# SparkFun_RTK_Facet_-_External_Connector.net
KiCad netlist of a schematic drawn in EAGLE
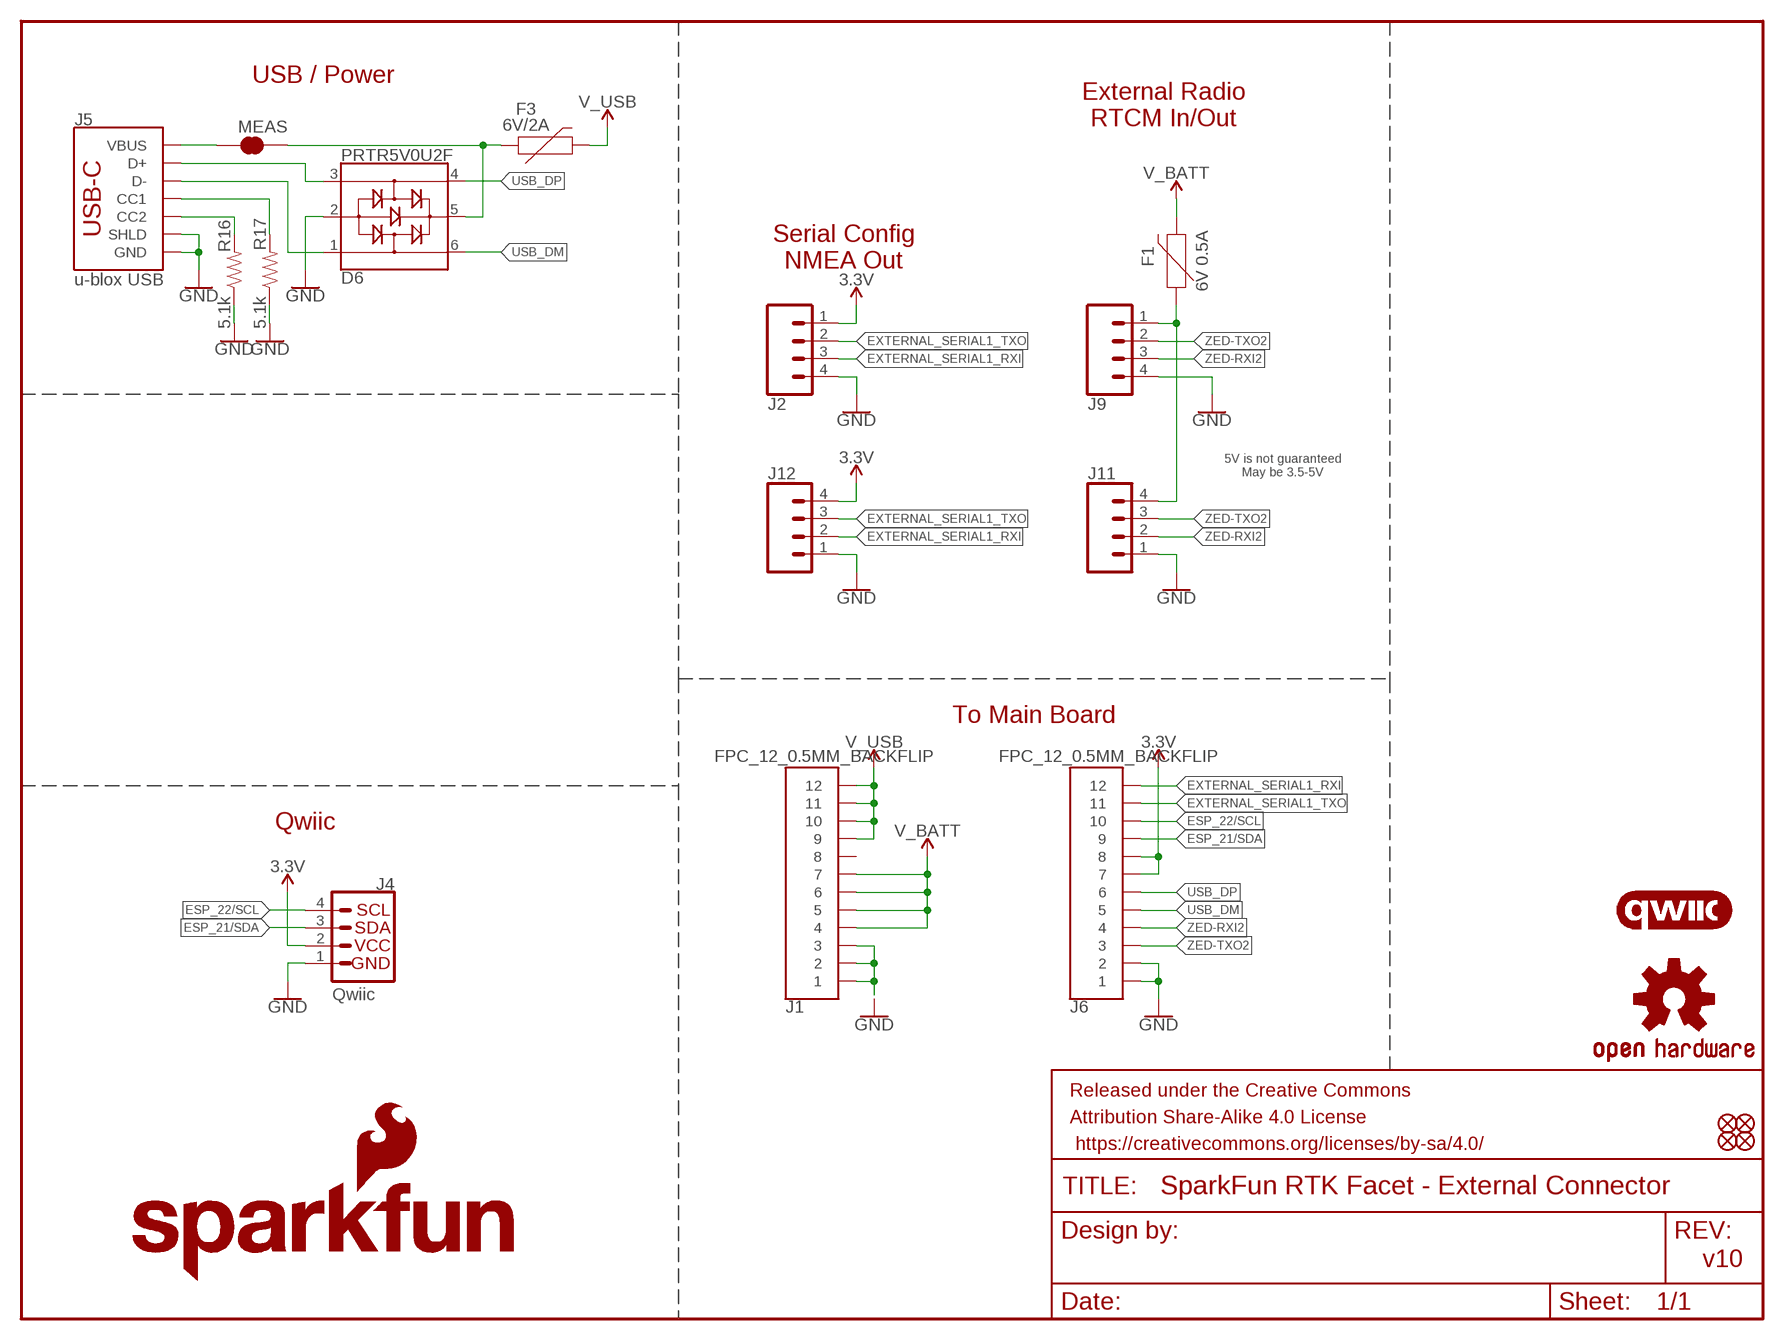
[diagram p0: schematic, sheet 1]

(export (version "E")
  (design (tool "Eeschema 10.0.6"))
  (components
    (comp (ref "D6")
      (value "PRTR5V0U2F")
      (footprint "eagle-import:SOT886")
      (libsource (lib "eagle-import") (part "PRTR5V0U2F"))
    )
    (comp (ref "F1")
      (value "6V 0.5A")
      (footprint "eagle-import:0805")
      (libsource (lib "eagle-import") (part "PPTC_6V500MA"))
    )
    (comp (ref "F3")
      (value "6V/2A")
      (footprint "eagle-import:1210")
      (libsource (lib "eagle-import") (part "PPTC_6V2A"))
    )
    (comp (ref "FRAME1")
      (value "FRAME-LETTER")
      (footprint "eagle-import:CREATIVE_COMMONS")
      (libsource (lib "eagle-import") (part "FRAME-LETTER"))
    )
    (comp (ref "J1")
      (value "FPC_12_0.5MM_BACKFLIP")
      (footprint "eagle-import:FPC_12_DOUBLESIDED_BACKFLIP")
      (libsource (lib "eagle-import") (part "FPC_12_0.5MM_BACKFLIP"))
    )
    (comp (ref "J2")
      (value "CONN_04JST-SMD-LOCKING")
      (footprint "eagle-import:JST-4-SMD-1.25MM-LOCKING")
      (libsource (lib "eagle-import") (part "CONN_04JST-SMD-LOCKING"))
    )
    (comp (ref "J4")
      (value "Qwiic")
      (footprint "eagle-import:JST04_1MM_RA")
      (libsource (lib "eagle-import") (part "I2C_STANDARDQWIIC"))
    )
    (comp (ref "J5")
      (value "u-blox USB")
      (footprint "eagle-import:USB-C-16P-2LAYER-PADS")
      (libsource (lib "eagle-import") (part "USB_C_2-LAYER_PADS"))
    )
    (comp (ref "J6")
      (value "FPC_12_0.5MM_BACKFLIP")
      (footprint "eagle-import:FPC_12_DOUBLESIDED_BACKFLIP")
      (libsource (lib "eagle-import") (part "FPC_12_0.5MM_BACKFLIP"))
    )
    (comp (ref "J9")
      (value "CONN_04JST-SMD-LOCKING")
      (footprint "eagle-import:JST-4-SMD-1.25MM-LOCKING")
      (libsource (lib "eagle-import") (part "CONN_04JST-SMD-LOCKING"))
    )
    (comp (ref "J11")
      (value "CONN_041X04_NO_SILK_NO_POP")
      (footprint "eagle-import:1X04_NO_SILK")
      (libsource (lib "eagle-import") (part "CONN_041X04_NO_SILK_NO_POP"))
    )
    (comp (ref "J12")
      (value "CONN_041X04_NO_SILK_NO_POP")
      (footprint "eagle-import:1X04_NO_SILK")
      (libsource (lib "eagle-import") (part "CONN_041X04_NO_SILK_NO_POP"))
    )
    (comp (ref "JP21")
      (value "FIDUCIALUFIDUCIAL")
      (footprint "eagle-import:FIDUCIAL-MICRO")
      (libsource (lib "eagle-import") (part "FIDUCIALUFIDUCIAL"))
    )
    (comp (ref "JP61")
      (value "FIDUCIALUFIDUCIAL")
      (footprint "eagle-import:FIDUCIAL-MICRO")
      (libsource (lib "eagle-import") (part "FIDUCIALUFIDUCIAL"))
    )
    (comp (ref "JP71")
      (value "FIDUCIALUFIDUCIAL")
      (footprint "eagle-import:FIDUCIAL-MICRO")
      (libsource (lib "eagle-import") (part "FIDUCIALUFIDUCIAL"))
    )
    (comp (ref "JP81")
      (value "FIDUCIALUFIDUCIAL")
      (footprint "eagle-import:FIDUCIAL-MICRO")
      (libsource (lib "eagle-import") (part "FIDUCIALUFIDUCIAL"))
    )
    (comp (ref "LOGO1")
      (value "OSHW-LOGOMINI")
      (footprint "eagle-import:OSHW-LOGO-MINI")
      (libsource (lib "eagle-import") (part "OSHW-LOGOMINI"))
    )
    (comp (ref "LOGO2")
      (value "SFE_LOGO_NAME_FLAME.1_INCH")
      (footprint "eagle-import:SFE_LOGO_NAME_FLAME_.1")
      (libsource (lib "eagle-import") (part "SFE_LOGO_NAME_FLAME.1_INCH"))
    )
    (comp (ref "LOGO3")
      (value "QWIIC_LOGO_CONNECTOR")
      (footprint "eagle-import:QWIIC_5.5MM")
      (libsource (lib "eagle-import") (part "QWIIC_LOGO_CONNECTOR"))
    )
    (comp (ref "MEAS")
      (value "JUMPER-COMBO_2_NC_TRACE")
      (footprint "eagle-import:COMBO-JUMPER_2_NC_TRACE")
      (libsource (lib "eagle-import") (part "JUMPER-COMBO_2_NC_TRACE"))
    )
    (comp (ref "R16")
      (value "5.1k")
      (footprint "eagle-import:0603")
      (libsource (lib "eagle-import") (part "5.1KOHM5.1KOHM-0603-1/10W-1%"))
    )
    (comp (ref "R17")
      (value "5.1k")
      (footprint "eagle-import:0603")
      (libsource (lib "eagle-import") (part "5.1KOHM5.1KOHM-0603-1/10W-1%"))
    )
  )
  (nets
    (net (code "1") (name "3.3V") (class "Default")
      (node (ref "J12") (pin "4") (pinfunction "4_4") (pintype "passive"))
      (node (ref "J2") (pin "1") (pinfunction "1_1") (pintype "passive"))
      (node (ref "J4") (pin "2") (pinfunction "2_2") (pintype "power_in"))
      (node (ref "J6") (pin "7") (pinfunction "7_7") (pintype "bidirectional"))
      (node (ref "J6") (pin "8") (pinfunction "8_8") (pintype "bidirectional"))
    )
    (net (code "2") (name "ESP_21{slash}SDA") (class "Default")
      (node (ref "J4") (pin "3") (pinfunction "3_3") (pintype "passive"))
      (node (ref "J6") (pin "9") (pinfunction "9_9") (pintype "bidirectional"))
    )
    (net (code "3") (name "ESP_22{slash}SCL") (class "Default")
      (node (ref "J4") (pin "4") (pinfunction "4_4") (pintype "passive"))
      (node (ref "J6") (pin "10") (pinfunction "10_10") (pintype "bidirectional"))
    )
    (net (code "4") (name "EXTERNAL_SERIAL1_RXI") (class "Default")
      (node (ref "J12") (pin "2") (pinfunction "2_2") (pintype "passive"))
      (node (ref "J2") (pin "3") (pinfunction "3_3") (pintype "passive"))
      (node (ref "J6") (pin "12") (pinfunction "12_12") (pintype "bidirectional"))
    )
    (net (code "5") (name "EXTERNAL_SERIAL1_TXO") (class "Default")
      (node (ref "J12") (pin "3") (pinfunction "3_3") (pintype "passive"))
      (node (ref "J2") (pin "2") (pinfunction "2_2") (pintype "passive"))
      (node (ref "J6") (pin "11") (pinfunction "11_11") (pintype "bidirectional"))
    )
    (net (code "6") (name "GND") (class "Default")
      (node (ref "D6") (pin "2") (pinfunction "2_2") (pintype "power_in"))
      (node (ref "J1") (pin "1") (pinfunction "1_1") (pintype "bidirectional"))
      (node (ref "J1") (pin "2") (pinfunction "2_2") (pintype "bidirectional"))
      (node (ref "J1") (pin "3") (pinfunction "3_3") (pintype "bidirectional"))
      (node (ref "J11") (pin "1") (pinfunction "1_1") (pintype "passive"))
      (node (ref "J12") (pin "1") (pinfunction "1_1") (pintype "passive"))
      (node (ref "J2") (pin "4") (pinfunction "4_4") (pintype "passive"))
      (node (ref "J4") (pin "1") (pinfunction "1_1") (pintype "power_in"))
      (node (ref "J5") (pin "GND") (pinfunction "GND_GND") (pintype "bidirectional"))
      (node (ref "J5") (pin "GND2") (pinfunction "GND_GND2") (pintype "bidirectional"))
      (node (ref "J5") (pin "SHLD1") (pinfunction "SHLD_SHLD1") (pintype "bidirectional"))
      (node (ref "J5") (pin "SHLD2") (pinfunction "SHLD_SHLD2") (pintype "bidirectional"))
      (node (ref "J5") (pin "SHLD3") (pinfunction "SHLD_SHLD3") (pintype "bidirectional"))
      (node (ref "J5") (pin "SHLD4") (pinfunction "SHLD_SHLD4") (pintype "bidirectional"))
      (node (ref "J6") (pin "1") (pinfunction "1_1") (pintype "bidirectional"))
      (node (ref "J6") (pin "2") (pinfunction "2_2") (pintype "bidirectional"))
      (node (ref "J9") (pin "4") (pinfunction "4_4") (pintype "passive"))
      (node (ref "R16") (pin "1") (pinfunction "1_1") (pintype "passive"))
      (node (ref "R17") (pin "1") (pinfunction "1_1") (pintype "passive"))
    )
    (net (code "7") (name "Net-(D6-Pad1)") (class "Default")
      (node (ref "D6") (pin "1") (pinfunction "1_1") (pintype "bidirectional"))
      (node (ref "J5") (pin "A7") (pinfunction "D-_A7") (pintype "bidirectional"))
      (node (ref "J5") (pin "B7") (pinfunction "D-_B7") (pintype "bidirectional"))
    )
    (net (code "8") (name "Net-(D6-Pad3)") (class "Default")
      (node (ref "D6") (pin "3") (pinfunction "3_3") (pintype "bidirectional"))
      (node (ref "J5") (pin "A6") (pinfunction "D+_A6") (pintype "bidirectional"))
      (node (ref "J5") (pin "B6") (pinfunction "D+_B6") (pintype "bidirectional"))
    )
    (net (code "9") (name "Net-(D6-Pad5)") (class "Default")
      (node (ref "D6") (pin "5") (pinfunction "5_5") (pintype "power_in"))
      (node (ref "F3") (pin "1") (pinfunction "1_1") (pintype "bidirectional"))
      (node (ref "MEAS") (pin "2") (pinfunction "2_2") (pintype "passive"))
      (node (ref "MEAS") (pin "4") (pinfunction "2_4") (pintype "passive"))
    )
    (net (code "10") (name "Net-(F1-Pad1)") (class "Default")
      (node (ref "F1") (pin "1") (pinfunction "1_1") (pintype "bidirectional"))
      (node (ref "J11") (pin "4") (pinfunction "4_4") (pintype "passive"))
      (node (ref "J9") (pin "1") (pinfunction "1_1") (pintype "passive"))
    )
    (net (code "11") (name "Net-(J5-CC1)") (class "Default")
      (node (ref "J5") (pin "A5") (pinfunction "CC1_A5") (pintype "bidirectional"))
      (node (ref "R17") (pin "2") (pinfunction "2_2") (pintype "passive"))
    )
    (net (code "12") (name "Net-(J5-CC2)") (class "Default")
      (node (ref "J5") (pin "B5") (pinfunction "CC2_B5") (pintype "bidirectional"))
      (node (ref "R16") (pin "2") (pinfunction "2_2") (pintype "passive"))
    )
    (net (code "13") (name "Net-(J5-VBUS-PadVBUS1)") (class "Default")
      (node (ref "J5") (pin "VBUS1") (pinfunction "VBUS_VBUS1") (pintype "bidirectional"))
      (node (ref "J5") (pin "VBUS2") (pinfunction "VBUS_VBUS2") (pintype "bidirectional"))
      (node (ref "MEAS") (pin "1") (pinfunction "1_1") (pintype "passive"))
      (node (ref "MEAS") (pin "3") (pinfunction "1_3") (pintype "passive"))
    )
    (net (code "14") (name "USB_DM") (class "Default")
      (node (ref "D6") (pin "6") (pinfunction "6_6") (pintype "bidirectional"))
      (node (ref "J6") (pin "5") (pinfunction "5_5") (pintype "bidirectional"))
    )
    (net (code "15") (name "USB_DP") (class "Default")
      (node (ref "D6") (pin "4") (pinfunction "4_4") (pintype "bidirectional"))
      (node (ref "J6") (pin "6") (pinfunction "6_6") (pintype "bidirectional"))
    )
    (net (code "16") (name "V_BATT") (class "Default")
      (node (ref "F1") (pin "2") (pinfunction "2_2") (pintype "bidirectional"))
      (node (ref "J1") (pin "4") (pinfunction "4_4") (pintype "bidirectional"))
      (node (ref "J1") (pin "5") (pinfunction "5_5") (pintype "bidirectional"))
      (node (ref "J1") (pin "6") (pinfunction "6_6") (pintype "bidirectional"))
      (node (ref "J1") (pin "7") (pinfunction "7_7") (pintype "bidirectional"))
    )
    (net (code "17") (name "V_USB") (class "Default")
      (node (ref "F3") (pin "2") (pinfunction "2_2") (pintype "bidirectional"))
      (node (ref "J1") (pin "10") (pinfunction "10_10") (pintype "bidirectional"))
      (node (ref "J1") (pin "11") (pinfunction "11_11") (pintype "bidirectional"))
      (node (ref "J1") (pin "12") (pinfunction "12_12") (pintype "bidirectional"))
      (node (ref "J1") (pin "9") (pinfunction "9_9") (pintype "bidirectional"))
    )
    (net (code "18") (name "ZED-RXI2") (class "Default")
      (node (ref "J11") (pin "2") (pinfunction "2_2") (pintype "passive"))
      (node (ref "J6") (pin "4") (pinfunction "4_4") (pintype "bidirectional"))
      (node (ref "J9") (pin "3") (pinfunction "3_3") (pintype "passive"))
    )
    (net (code "19") (name "ZED-TXO2") (class "Default")
      (node (ref "J11") (pin "3") (pinfunction "3_3") (pintype "passive"))
      (node (ref "J6") (pin "3") (pinfunction "3_3") (pintype "bidirectional"))
      (node (ref "J9") (pin "2") (pinfunction "2_2") (pintype "passive"))
    )
    (net (code "20") (name "unconnected-(J1-Pad8)") (class "Default")
      (node (ref "J1") (pin "8") (pinfunction "8_8") (pintype "bidirectional"))
    )
  )
)
